# Template_Komponen.net
KiCad netlist of a schematic drawn in EAGLE
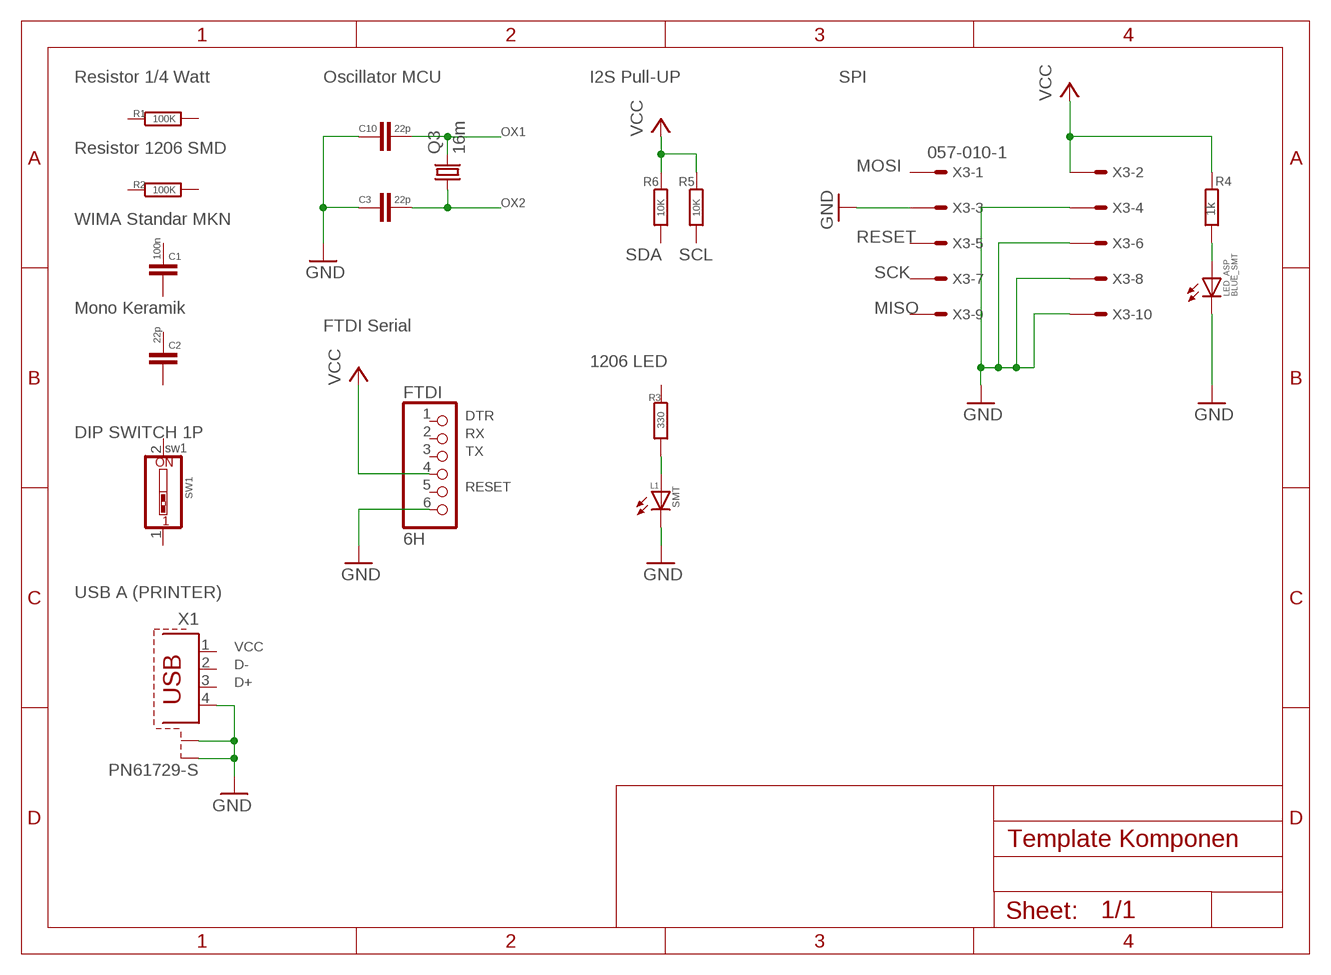
[diagram p0: schematic, sheet 1]

(export (version "E")
  (design (tool "Eeschema 10.0.6"))
  (components
    (comp (ref "C1")
      (value "100n")
      (footprint "eagle-import:C050-025X075")
      (libsource (lib "eagle-import") (part "C-EU050-025X075"))
    )
    (comp (ref "C2")
      (value "22p")
      (footprint "eagle-import:C050-024X044")
      (libsource (lib "eagle-import") (part "C-EU050-024X044"))
    )
    (comp (ref "C3")
      (value "22p")
      (footprint "eagle-import:C1206")
      (libsource (lib "eagle-import") (part "C-EUC1206"))
    )
    (comp (ref "C10")
      (value "22p")
      (footprint "eagle-import:C1206")
      (libsource (lib "eagle-import") (part "C-EUC1206"))
    )
    (comp (ref "FTDI")
      (value "6H")
      (footprint "eagle-import:1X06")
      (libsource (lib "eagle-import") (part "PINHD-1X6"))
    )
    (comp (ref "L1")
      (value "SMT")
      (footprint "eagle-import:1206")
      (libsource (lib "eagle-import") (part "LEDSMT1206"))
    )
    (comp (ref "LED_ASP")
      (value "BLUE_SMT")
      (footprint "eagle-import:1206")
      (libsource (lib "eagle-import") (part "LEDSMT1206"))
    )
    (comp (ref "Q3")
      (value "16m")
      (footprint "eagle-import:HC49UP")
      (libsource (lib "eagle-import") (part "CRYSTALHC49UP"))
    )
    (comp (ref "R1")
      (value "100K")
      (footprint "eagle-import:0204_7")
      (libsource (lib "eagle-import") (part "R-EU_0204/7"))
    )
    (comp (ref "R2")
      (value "100K")
      (footprint "eagle-import:R1206")
      (libsource (lib "eagle-import") (part "R-EU_R1206"))
    )
    (comp (ref "R3")
      (value "330")
      (footprint "eagle-import:R1206")
      (libsource (lib "eagle-import") (part "R-EU_R1206"))
    )
    (comp (ref "R4")
      (value "1k")
      (footprint "eagle-import:R1206")
      (libsource (lib "eagle-import") (part "R-EU_R1206"))
    )
    (comp (ref "R5")
      (value "10K")
      (footprint "eagle-import:0204_7")
      (libsource (lib "eagle-import") (part "R-EU_0204/7"))
    )
    (comp (ref "R6")
      (value "10K")
      (footprint "eagle-import:0204_7")
      (libsource (lib "eagle-import") (part "R-EU_0204/7"))
    )
    (comp (ref "SW1")
      (value "sw1")
      (footprint "eagle-import:EDG-01")
      (libsource (lib "eagle-import") (part "SW_DIP-1"))
    )
    (comp (ref "X1")
      (value "PN61729-S")
      (footprint "eagle-import:PN61729-S")
      (libsource (lib "eagle-import") (part "PN61729-S"))
    )
    (comp (ref "X3")
      (value "057-010-1")
      (footprint "eagle-import:057-010-1")
      (libsource (lib "eagle-import") (part "057-010-1"))
    )
  )
  (nets
    (net (code "1") (name "/OX1") (class "Default")
      (node (ref "C10") (pin "2") (pinfunction "2_2") (pintype "passive"))
      (node (ref "Q3") (pin "2") (pinfunction "2_2") (pintype "passive"))
    )
    (net (code "2") (name "/OX2") (class "Default")
      (node (ref "C3") (pin "2") (pinfunction "2_2") (pintype "passive"))
      (node (ref "Q3") (pin "1") (pinfunction "1_1") (pintype "passive"))
    )
    (net (code "3") (name "GND") (class "Default")
      (node (ref "C10") (pin "1") (pinfunction "1_1") (pintype "passive"))
      (node (ref "C3") (pin "1") (pinfunction "1_1") (pintype "passive"))
      (node (ref "FTDI") (pin "6") (pinfunction "6_6") (pintype "passive"))
      (node (ref "L1") (pin "C") (pinfunction "C_C") (pintype "passive"))
      (node (ref "LED_ASP") (pin "C") (pinfunction "C_C") (pintype "passive"))
      (node (ref "X1") (pin "4") (pinfunction "4_4") (pintype "passive"))
      (node (ref "X1") (pin "S1") (pinfunction "S1_S1") (pintype "passive"))
      (node (ref "X1") (pin "S2") (pinfunction "S2_S2") (pintype "passive"))
      (node (ref "X3") (pin "10") (pinfunction "S_10") (pintype "passive"))
      (node (ref "X3") (pin "3") (pinfunction "S_3") (pintype "passive"))
      (node (ref "X3") (pin "4") (pinfunction "S_4") (pintype "passive"))
      (node (ref "X3") (pin "6") (pinfunction "S_6") (pintype "passive"))
      (node (ref "X3") (pin "8") (pinfunction "S_8") (pintype "passive"))
    )
    (net (code "4") (name "Net-(L1-PadA)") (class "Default")
      (node (ref "L1") (pin "A") (pinfunction "A_A") (pintype "passive"))
      (node (ref "R3") (pin "2") (pinfunction "2_2") (pintype "passive"))
    )
    (net (code "5") (name "Net-(LED_ASP-PadA)") (class "Default")
      (node (ref "LED_ASP") (pin "A") (pinfunction "A_A") (pintype "passive"))
      (node (ref "R4") (pin "2") (pinfunction "2_2") (pintype "passive"))
    )
    (net (code "6") (name "VCC") (class "Default")
      (node (ref "FTDI") (pin "4") (pinfunction "4_4") (pintype "passive"))
      (node (ref "R4") (pin "1") (pinfunction "1_1") (pintype "passive"))
      (node (ref "R5") (pin "1") (pinfunction "1_1") (pintype "passive"))
      (node (ref "R6") (pin "1") (pinfunction "1_1") (pintype "passive"))
      (node (ref "X3") (pin "2") (pinfunction "S_2") (pintype "passive"))
    )
    (net (code "7") (name "unconnected-(C1-Pad1)") (class "Default")
      (node (ref "C1") (pin "1") (pinfunction "1_1") (pintype "passive"))
    )
    (net (code "8") (name "unconnected-(C1-Pad2)") (class "Default")
      (node (ref "C1") (pin "2") (pinfunction "2_2") (pintype "passive"))
    )
    (net (code "9") (name "unconnected-(C2-Pad1)") (class "Default")
      (node (ref "C2") (pin "1") (pinfunction "1_1") (pintype "passive"))
    )
    (net (code "10") (name "unconnected-(C2-Pad2)") (class "Default")
      (node (ref "C2") (pin "2") (pinfunction "2_2") (pintype "passive"))
    )
    (net (code "11") (name "unconnected-(FTDI-Pad1)") (class "Default")
      (node (ref "FTDI") (pin "1") (pinfunction "1_1") (pintype "passive"))
    )
    (net (code "12") (name "unconnected-(FTDI-Pad2)") (class "Default")
      (node (ref "FTDI") (pin "2") (pinfunction "2_2") (pintype "passive"))
    )
    (net (code "13") (name "unconnected-(FTDI-Pad3)") (class "Default")
      (node (ref "FTDI") (pin "3") (pinfunction "3_3") (pintype "passive"))
    )
    (net (code "14") (name "unconnected-(FTDI-Pad5)") (class "Default")
      (node (ref "FTDI") (pin "5") (pinfunction "5_5") (pintype "passive"))
    )
    (net (code "15") (name "unconnected-(R1-Pad1)") (class "Default")
      (node (ref "R1") (pin "1") (pinfunction "1_1") (pintype "passive"))
    )
    (net (code "16") (name "unconnected-(R1-Pad2)") (class "Default")
      (node (ref "R1") (pin "2") (pinfunction "2_2") (pintype "passive"))
    )
    (net (code "17") (name "unconnected-(R2-Pad1)") (class "Default")
      (node (ref "R2") (pin "1") (pinfunction "1_1") (pintype "passive"))
    )
    (net (code "18") (name "unconnected-(R2-Pad2)") (class "Default")
      (node (ref "R2") (pin "2") (pinfunction "2_2") (pintype "passive"))
    )
    (net (code "19") (name "unconnected-(R3-Pad1)") (class "Default")
      (node (ref "R3") (pin "1") (pinfunction "1_1") (pintype "passive"))
    )
    (net (code "20") (name "unconnected-(R5-Pad2)") (class "Default")
      (node (ref "R5") (pin "2") (pinfunction "2_2") (pintype "passive"))
    )
    (net (code "21") (name "unconnected-(R6-Pad2)") (class "Default")
      (node (ref "R6") (pin "2") (pinfunction "2_2") (pintype "passive"))
    )
    (net (code "22") (name "unconnected-(SW1-Pad1)") (class "Default")
      (node (ref "SW1") (pin "1") (pinfunction "1_1") (pintype "passive"))
    )
    (net (code "23") (name "unconnected-(SW1-Pad2)") (class "Default")
      (node (ref "SW1") (pin "2") (pinfunction "2_2") (pintype "passive"))
    )
    (net (code "24") (name "unconnected-(X1-Pad1)") (class "Default")
      (node (ref "X1") (pin "1") (pinfunction "1_1") (pintype "passive"))
    )
    (net (code "25") (name "unconnected-(X1-Pad2)") (class "Default")
      (node (ref "X1") (pin "2") (pinfunction "2_2") (pintype "passive"))
    )
    (net (code "26") (name "unconnected-(X1-Pad3)") (class "Default")
      (node (ref "X1") (pin "3") (pinfunction "3_3") (pintype "passive"))
    )
    (net (code "27") (name "unconnected-(X3A-S-Pad1)") (class "Default")
      (node (ref "X3") (pin "1") (pinfunction "S_1") (pintype "passive"))
    )
    (net (code "28") (name "unconnected-(X3F-S-Pad5)") (class "Default")
      (node (ref "X3") (pin "5") (pinfunction "S_5") (pintype "passive"))
    )
    (net (code "29") (name "unconnected-(X3H-S-Pad7)") (class "Default")
      (node (ref "X3") (pin "7") (pinfunction "S_7") (pintype "passive"))
    )
    (net (code "30") (name "unconnected-(X3J-S-Pad9)") (class "Default")
      (node (ref "X3") (pin "9") (pinfunction "S_9") (pintype "passive"))
    )
  )
)
